# Arduino_Uno_Sheild.net
KiCad netlist of a schematic drawn in EAGLE
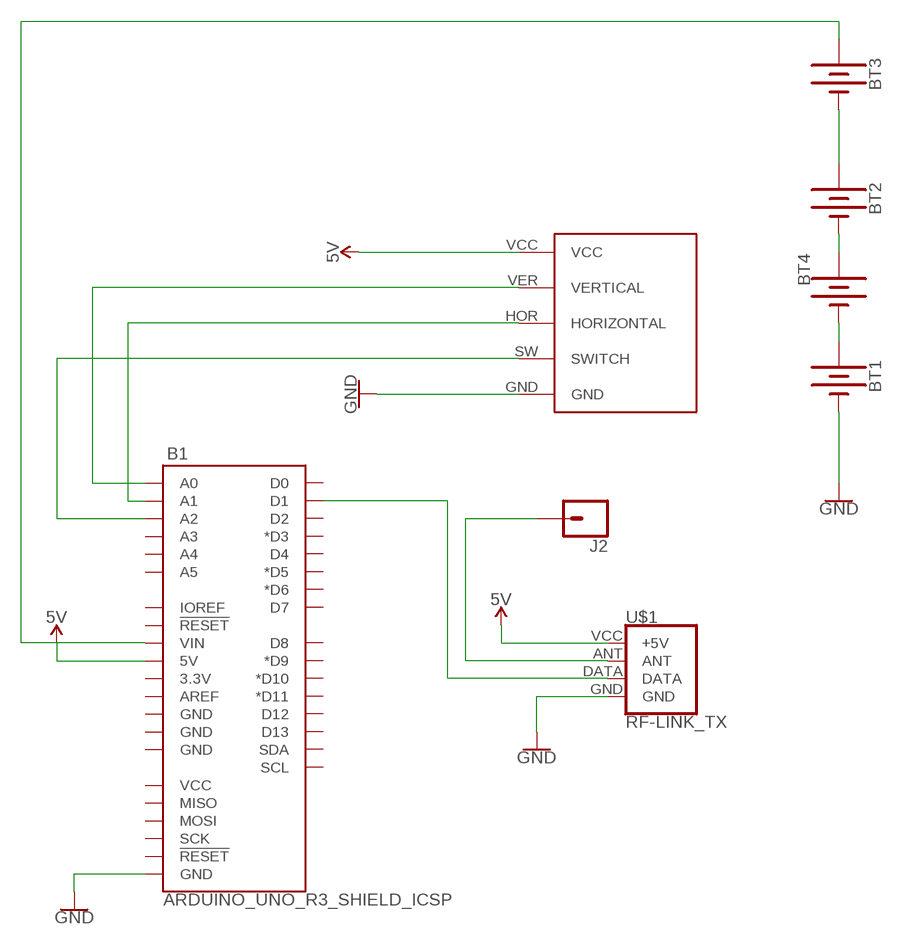
[diagram p0: schematic, sheet 1]

(export (version "E")
  (design (tool "Eeschema 10.0.6"))
  (components
    (comp (ref "B1")
      (value "ARDUINO_UNO_R3_SHIELD_ICSP")
      (footprint "eagle-import:UNO_R3_SHIELD_ICSP")
      (libsource (lib "eagle-import") (part "ARDUINO_UNO_R3_SHIELD_ICSP"))
    )
    (comp (ref "BT1")
      (value "BATTERY-AAA")
      (footprint "eagle-import:BATTERY-AAA")
      (libsource (lib "eagle-import") (part "BATTERY-AAA"))
    )
    (comp (ref "BT2")
      (value "BATTERY-AAA")
      (footprint "eagle-import:BATTERY-AAA")
      (libsource (lib "eagle-import") (part "BATTERY-AAA"))
    )
    (comp (ref "BT3")
      (value "BATTERY-AAA")
      (footprint "eagle-import:BATTERY-AAA")
      (libsource (lib "eagle-import") (part "BATTERY-AAA"))
    )
    (comp (ref "BT4")
      (value "BATTERY-AAA")
      (footprint "eagle-import:BATTERY-AAA")
      (libsource (lib "eagle-import") (part "BATTERY-AAA"))
    )
    (comp (ref "J2")
      (value "CONN_01POGOPIN_HOLE_0.58")
      (footprint "eagle-import:1X01_POGOPIN_HOLE_0.58_DIA")
      (libsource (lib "eagle-import") (part "CONN_01POGOPIN_HOLE_0.58"))
    )
    (comp (ref "JOYSTICK1")
      (value "JOYSTICK")
      (footprint "eagle-import:JOYSTICK")
      (libsource (lib "eagle-import") (part "JOYSTICK"))
    )
    (comp (ref "U$1")
      (value "RF-LINK_TX")
      (footprint "eagle-import:RF-LINK_TX")
      (libsource (lib "eagle-import") (part "RF-LINK_TX"))
    )
  )
  (nets
    (net (code "1") (name "5V") (class "Default")
      (node (ref "B1") (pin "5V") (pinfunction "5V_5V") (pintype "bidirectional"))
      (node (ref "JOYSTICK1") (pin "VCC") (pinfunction "VCC_VCC") (pintype "bidirectional"))
      (node (ref "U$1") (pin "VCC") (pinfunction "+5V_VCC") (pintype "power_in"))
    )
    (net (code "2") (name "GND") (class "Default")
      (node (ref "B1") (pin "GND_ICSP") (pinfunction "GND_GND_ICSP") (pintype "bidirectional"))
      (node (ref "BT1") (pin "GND@1") (pinfunction "-_GND@1") (pintype "power_in"))
      (node (ref "JOYSTICK1") (pin "GND") (pinfunction "GND_GND") (pintype "bidirectional"))
      (node (ref "U$1") (pin "GND") (pinfunction "GND_GND") (pintype "power_in"))
    )
    (net (code "3") (name "Net-(B1-D1)") (class "Default")
      (node (ref "B1") (pin "TX") (pinfunction "D1_TX") (pintype "bidirectional"))
      (node (ref "U$1") (pin "DATA") (pinfunction "DATA_DATA") (pintype "input"))
    )
    (net (code "4") (name "Net-(BT1-+)") (class "Default")
      (node (ref "BT1") (pin "PWR@1") (pinfunction "+_PWR@1") (pintype "power_in"))
      (node (ref "BT4") (pin "GND@1") (pinfunction "-_GND@1") (pintype "power_in"))
    )
    (net (code "5") (name "Net-(BT2-+)") (class "Default")
      (node (ref "BT2") (pin "PWR@1") (pinfunction "+_PWR@1") (pintype "power_in"))
      (node (ref "BT3") (pin "GND@1") (pinfunction "-_GND@1") (pintype "power_in"))
    )
    (net (code "6") (name "Net-(BT2--)") (class "Default")
      (node (ref "BT2") (pin "GND@1") (pinfunction "-_GND@1") (pintype "power_in"))
      (node (ref "BT4") (pin "PWR@1") (pinfunction "+_PWR@1") (pintype "power_in"))
    )
    (net (code "7") (name "Net-(BT3-+)") (class "Default")
      (node (ref "B1") (pin "VIN") (pinfunction "VIN_VIN") (pintype "bidirectional"))
      (node (ref "BT3") (pin "PWR@1") (pinfunction "+_PWR@1") (pintype "power_in"))
    )
    (net (code "8") (name "Net-(J2-Pad1)") (class "Default")
      (node (ref "J2") (pin "1") (pinfunction "1_1") (pintype "passive"))
      (node (ref "U$1") (pin "ANT") (pinfunction "ANT_ANT") (pintype "passive"))
    )
    (net (code "9") (name "Net-(JOYSTICK1-HORIZONTAL)") (class "Default")
      (node (ref "B1") (pin "A1") (pinfunction "A1_A1") (pintype "bidirectional"))
      (node (ref "JOYSTICK1") (pin "HOR") (pinfunction "HORIZONTAL_HOR") (pintype "bidirectional"))
    )
    (net (code "10") (name "Net-(JOYSTICK1-SWITCH)") (class "Default")
      (node (ref "B1") (pin "A2") (pinfunction "A2_A2") (pintype "bidirectional"))
      (node (ref "JOYSTICK1") (pin "SW") (pinfunction "SWITCH_SW") (pintype "bidirectional"))
    )
    (net (code "11") (name "Net-(JOYSTICK1-VERTICAL)") (class "Default")
      (node (ref "B1") (pin "A0") (pinfunction "A0_A0") (pintype "bidirectional"))
      (node (ref "JOYSTICK1") (pin "VER") (pinfunction "VERTICAL_VER") (pintype "bidirectional"))
    )
    (net (code "12") (name "unconnected-(B1-*D3-PadD3)") (class "Default")
      (node (ref "B1") (pin "D3") (pinfunction "*D3_D3") (pintype "bidirectional"))
    )
    (net (code "13") (name "unconnected-(B1-*D5-PadD5)") (class "Default")
      (node (ref "B1") (pin "D5") (pinfunction "*D5_D5") (pintype "bidirectional"))
    )
    (net (code "14") (name "unconnected-(B1-*D6-PadD6)") (class "Default")
      (node (ref "B1") (pin "D6") (pinfunction "*D6_D6") (pintype "bidirectional"))
    )
    (net (code "15") (name "unconnected-(B1-*D9-PadD9)") (class "Default")
      (node (ref "B1") (pin "D9") (pinfunction "*D9_D9") (pintype "bidirectional"))
    )
    (net (code "16") (name "unconnected-(B1-*D10-PadD10)") (class "Default")
      (node (ref "B1") (pin "D10") (pinfunction "*D10_D10") (pintype "bidirectional"))
    )
    (net (code "17") (name "unconnected-(B1-*D11-PadD11)") (class "Default")
      (node (ref "B1") (pin "D11") (pinfunction "*D11_D11") (pintype "bidirectional"))
    )
    (net (code "18") (name "unconnected-(B1-D0-PadRX)") (class "Default")
      (node (ref "B1") (pin "RX") (pinfunction "D0_RX") (pintype "bidirectional"))
    )
    (net (code "19") (name "unconnected-(B1-GND-PadGND@0)") (class "Default")
      (node (ref "B1") (pin "GND@0") (pinfunction "GND_GND@0") (pintype "bidirectional"))
    )
    (net (code "20") (name "unconnected-(B1-GND-PadGND@1)") (class "Default")
      (node (ref "B1") (pin "GND@1") (pinfunction "GND_GND@1") (pintype "bidirectional"))
    )
    (net (code "21") (name "unconnected-(B1-GND-PadGND@2)") (class "Default")
      (node (ref "B1") (pin "GND@2") (pinfunction "GND_GND@2") (pintype "bidirectional"))
    )
    (net (code "22") (name "unconnected-(B1-Pad3.3V)") (class "Default")
      (node (ref "B1") (pin "3.3V") (pinfunction "3.3V_3.3V") (pintype "bidirectional"))
    )
    (net (code "23") (name "unconnected-(B1-PadA3)") (class "Default")
      (node (ref "B1") (pin "A3") (pinfunction "A3_A3") (pintype "bidirectional"))
    )
    (net (code "24") (name "unconnected-(B1-PadA4)") (class "Default")
      (node (ref "B1") (pin "A4") (pinfunction "A4_A4") (pintype "bidirectional"))
    )
    (net (code "25") (name "unconnected-(B1-PadA5)") (class "Default")
      (node (ref "B1") (pin "A5") (pinfunction "A5_A5") (pintype "bidirectional"))
    )
    (net (code "26") (name "unconnected-(B1-PadAREF)") (class "Default")
      (node (ref "B1") (pin "AREF") (pinfunction "AREF_AREF") (pintype "bidirectional"))
    )
    (net (code "27") (name "unconnected-(B1-PadD2)") (class "Default")
      (node (ref "B1") (pin "D2") (pinfunction "D2_D2") (pintype "bidirectional"))
    )
    (net (code "28") (name "unconnected-(B1-PadD4)") (class "Default")
      (node (ref "B1") (pin "D4") (pinfunction "D4_D4") (pintype "bidirectional"))
    )
    (net (code "29") (name "unconnected-(B1-PadD7)") (class "Default")
      (node (ref "B1") (pin "D7") (pinfunction "D7_D7") (pintype "bidirectional"))
    )
    (net (code "30") (name "unconnected-(B1-PadD8)") (class "Default")
      (node (ref "B1") (pin "D8") (pinfunction "D8_D8") (pintype "bidirectional"))
    )
    (net (code "31") (name "unconnected-(B1-PadD12)") (class "Default")
      (node (ref "B1") (pin "D12") (pinfunction "D12_D12") (pintype "bidirectional"))
    )
    (net (code "32") (name "unconnected-(B1-PadD13)") (class "Default")
      (node (ref "B1") (pin "D13") (pinfunction "D13_D13") (pintype "bidirectional"))
    )
    (net (code "33") (name "unconnected-(B1-PadIOREF)") (class "Default")
      (node (ref "B1") (pin "IOREF") (pinfunction "IOREF_IOREF") (pintype "bidirectional"))
    )
    (net (code "34") (name "unconnected-(B1-PadMISO)") (class "Default")
      (node (ref "B1") (pin "MISO") (pinfunction "MISO_MISO") (pintype "bidirectional"))
    )
    (net (code "35") (name "unconnected-(B1-PadMOSI)") (class "Default")
      (node (ref "B1") (pin "MOSI") (pinfunction "MOSI_MOSI") (pintype "bidirectional"))
    )
    (net (code "36") (name "unconnected-(B1-PadSCK)") (class "Default")
      (node (ref "B1") (pin "SCK") (pinfunction "SCK_SCK") (pintype "bidirectional"))
    )
    (net (code "37") (name "unconnected-(B1-PadSCL)") (class "Default")
      (node (ref "B1") (pin "SCL") (pinfunction "SCL_SCL") (pintype "bidirectional"))
    )
    (net (code "38") (name "unconnected-(B1-PadSDA)") (class "Default")
      (node (ref "B1") (pin "SDA") (pinfunction "SDA_SDA") (pintype "bidirectional"))
    )
    (net (code "39") (name "unconnected-(B1-VCC-Pad5V_ICSP)") (class "Default")
      (node (ref "B1") (pin "5V_ICSP") (pinfunction "VCC_5V_ICSP") (pintype "bidirectional"))
    )
    (net (code "40") (name "unconnected-(B1-~{RESET}-PadRES)") (class "Default")
      (node (ref "B1") (pin "RES") (pinfunction "~{RESET}_RES") (pintype "bidirectional"))
    )
    (net (code "41") (name "unconnected-(B1-~{RESET}-PadRST_ICSP)") (class "Default")
      (node (ref "B1") (pin "RST_ICSP") (pinfunction "~{RESET}_RST_ICSP") (pintype "bidirectional"))
    )
  )
)
